# LED-Lamp-2-SMD-50leds.net
KiCad netlist of a schematic drawn in EAGLE
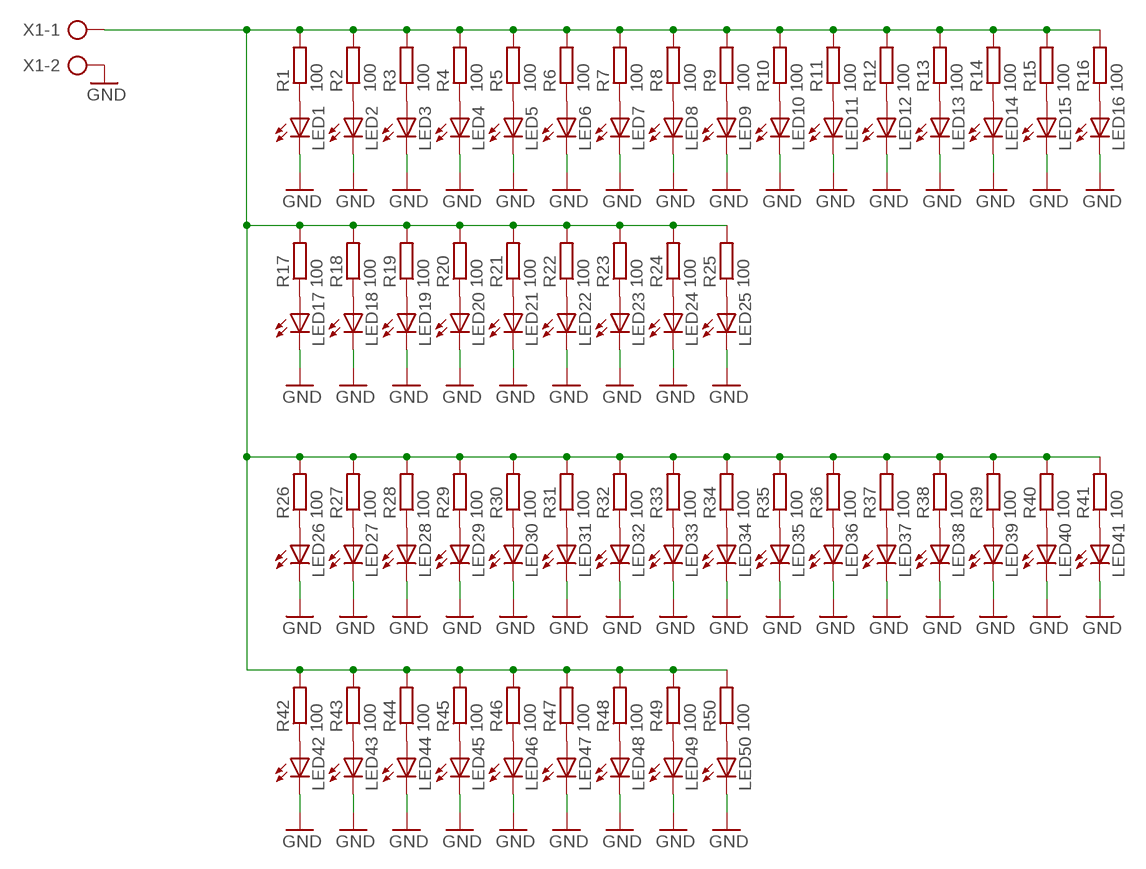
[diagram p0: schematic, sheet 1]

(export (version "E")
  (design (tool "Eeschema 10.0.6"))
  (components
    (comp (ref "LED1")
      (value "LEDSML0805")
      (footprint "eagle-import:SML0805")
      (libsource (lib "eagle-import") (part "LEDSML0805"))
    )
    (comp (ref "LED2")
      (value "LEDSML0805")
      (footprint "eagle-import:SML0805")
      (libsource (lib "eagle-import") (part "LEDSML0805"))
    )
    (comp (ref "LED3")
      (value "LEDSML0805")
      (footprint "eagle-import:SML0805")
      (libsource (lib "eagle-import") (part "LEDSML0805"))
    )
    (comp (ref "LED4")
      (value "LEDSML0805")
      (footprint "eagle-import:SML0805")
      (libsource (lib "eagle-import") (part "LEDSML0805"))
    )
    (comp (ref "LED5")
      (value "LEDSML0805")
      (footprint "eagle-import:SML0805")
      (libsource (lib "eagle-import") (part "LEDSML0805"))
    )
    (comp (ref "LED6")
      (value "LEDSML0805")
      (footprint "eagle-import:SML0805")
      (libsource (lib "eagle-import") (part "LEDSML0805"))
    )
    (comp (ref "LED7")
      (value "LEDSML0805")
      (footprint "eagle-import:SML0805")
      (libsource (lib "eagle-import") (part "LEDSML0805"))
    )
    (comp (ref "LED8")
      (value "LEDSML0805")
      (footprint "eagle-import:SML0805")
      (libsource (lib "eagle-import") (part "LEDSML0805"))
    )
    (comp (ref "LED9")
      (value "LEDSML0805")
      (footprint "eagle-import:SML0805")
      (libsource (lib "eagle-import") (part "LEDSML0805"))
    )
    (comp (ref "LED10")
      (value "LEDSML0805")
      (footprint "eagle-import:SML0805")
      (libsource (lib "eagle-import") (part "LEDSML0805"))
    )
    (comp (ref "LED11")
      (value "LEDSML0805")
      (footprint "eagle-import:SML0805")
      (libsource (lib "eagle-import") (part "LEDSML0805"))
    )
    (comp (ref "LED12")
      (value "LEDSML0805")
      (footprint "eagle-import:SML0805")
      (libsource (lib "eagle-import") (part "LEDSML0805"))
    )
    (comp (ref "LED13")
      (value "LEDSML0805")
      (footprint "eagle-import:SML0805")
      (libsource (lib "eagle-import") (part "LEDSML0805"))
    )
    (comp (ref "LED14")
      (value "LEDSML0805")
      (footprint "eagle-import:SML0805")
      (libsource (lib "eagle-import") (part "LEDSML0805"))
    )
    (comp (ref "LED15")
      (value "LEDSML0805")
      (footprint "eagle-import:SML0805")
      (libsource (lib "eagle-import") (part "LEDSML0805"))
    )
    (comp (ref "LED16")
      (value "LEDSML0805")
      (footprint "eagle-import:SML0805")
      (libsource (lib "eagle-import") (part "LEDSML0805"))
    )
    (comp (ref "LED17")
      (value "LEDSML0805")
      (footprint "eagle-import:SML0805")
      (libsource (lib "eagle-import") (part "LEDSML0805"))
    )
    (comp (ref "LED18")
      (value "LEDSML0805")
      (footprint "eagle-import:SML0805")
      (libsource (lib "eagle-import") (part "LEDSML0805"))
    )
    (comp (ref "LED19")
      (value "LEDSML0805")
      (footprint "eagle-import:SML0805")
      (libsource (lib "eagle-import") (part "LEDSML0805"))
    )
    (comp (ref "LED20")
      (value "LEDSML0805")
      (footprint "eagle-import:SML0805")
      (libsource (lib "eagle-import") (part "LEDSML0805"))
    )
    (comp (ref "LED21")
      (value "LEDSML0805")
      (footprint "eagle-import:SML0805")
      (libsource (lib "eagle-import") (part "LEDSML0805"))
    )
    (comp (ref "LED22")
      (value "LEDSML0805")
      (footprint "eagle-import:SML0805")
      (libsource (lib "eagle-import") (part "LEDSML0805"))
    )
    (comp (ref "LED23")
      (value "LEDSML0805")
      (footprint "eagle-import:SML0805")
      (libsource (lib "eagle-import") (part "LEDSML0805"))
    )
    (comp (ref "LED24")
      (value "LEDSML0805")
      (footprint "eagle-import:SML0805")
      (libsource (lib "eagle-import") (part "LEDSML0805"))
    )
    (comp (ref "LED25")
      (value "LEDSML0805")
      (footprint "eagle-import:SML0805")
      (libsource (lib "eagle-import") (part "LEDSML0805"))
    )
    (comp (ref "LED26")
      (value "LEDSML0805")
      (footprint "eagle-import:SML0805")
      (libsource (lib "eagle-import") (part "LEDSML0805"))
    )
    (comp (ref "LED27")
      (value "LEDSML0805")
      (footprint "eagle-import:SML0805")
      (libsource (lib "eagle-import") (part "LEDSML0805"))
    )
    (comp (ref "LED28")
      (value "LEDSML0805")
      (footprint "eagle-import:SML0805")
      (libsource (lib "eagle-import") (part "LEDSML0805"))
    )
    (comp (ref "LED29")
      (value "LEDSML0805")
      (footprint "eagle-import:SML0805")
      (libsource (lib "eagle-import") (part "LEDSML0805"))
    )
    (comp (ref "LED30")
      (value "LEDSML0805")
      (footprint "eagle-import:SML0805")
      (libsource (lib "eagle-import") (part "LEDSML0805"))
    )
    (comp (ref "LED31")
      (value "LEDSML0805")
      (footprint "eagle-import:SML0805")
      (libsource (lib "eagle-import") (part "LEDSML0805"))
    )
    (comp (ref "LED32")
      (value "LEDSML0805")
      (footprint "eagle-import:SML0805")
      (libsource (lib "eagle-import") (part "LEDSML0805"))
    )
    (comp (ref "LED33")
      (value "LEDSML0805")
      (footprint "eagle-import:SML0805")
      (libsource (lib "eagle-import") (part "LEDSML0805"))
    )
    (comp (ref "LED34")
      (value "LEDSML0805")
      (footprint "eagle-import:SML0805")
      (libsource (lib "eagle-import") (part "LEDSML0805"))
    )
    (comp (ref "LED35")
      (value "LEDSML0805")
      (footprint "eagle-import:SML0805")
      (libsource (lib "eagle-import") (part "LEDSML0805"))
    )
    (comp (ref "LED36")
      (value "LEDSML0805")
      (footprint "eagle-import:SML0805")
      (libsource (lib "eagle-import") (part "LEDSML0805"))
    )
    (comp (ref "LED37")
      (value "LEDSML0805")
      (footprint "eagle-import:SML0805")
      (libsource (lib "eagle-import") (part "LEDSML0805"))
    )
    (comp (ref "LED38")
      (value "LEDSML0805")
      (footprint "eagle-import:SML0805")
      (libsource (lib "eagle-import") (part "LEDSML0805"))
    )
    (comp (ref "LED39")
      (value "LEDSML0805")
      (footprint "eagle-import:SML0805")
      (libsource (lib "eagle-import") (part "LEDSML0805"))
    )
    (comp (ref "LED40")
      (value "LEDSML0805")
      (footprint "eagle-import:SML0805")
      (libsource (lib "eagle-import") (part "LEDSML0805"))
    )
    (comp (ref "LED41")
      (value "LEDSML0805")
      (footprint "eagle-import:SML0805")
      (libsource (lib "eagle-import") (part "LEDSML0805"))
    )
    (comp (ref "LED42")
      (value "LEDSML0805")
      (footprint "eagle-import:SML0805")
      (libsource (lib "eagle-import") (part "LEDSML0805"))
    )
    (comp (ref "LED43")
      (value "LEDSML0805")
      (footprint "eagle-import:SML0805")
      (libsource (lib "eagle-import") (part "LEDSML0805"))
    )
    (comp (ref "LED44")
      (value "LEDSML0805")
      (footprint "eagle-import:SML0805")
      (libsource (lib "eagle-import") (part "LEDSML0805"))
    )
    (comp (ref "LED45")
      (value "LEDSML0805")
      (footprint "eagle-import:SML0805")
      (libsource (lib "eagle-import") (part "LEDSML0805"))
    )
    (comp (ref "LED46")
      (value "LEDSML0805")
      (footprint "eagle-import:SML0805")
      (libsource (lib "eagle-import") (part "LEDSML0805"))
    )
    (comp (ref "LED47")
      (value "LEDSML0805")
      (footprint "eagle-import:SML0805")
      (libsource (lib "eagle-import") (part "LEDSML0805"))
    )
    (comp (ref "LED48")
      (value "LEDSML0805")
      (footprint "eagle-import:SML0805")
      (libsource (lib "eagle-import") (part "LEDSML0805"))
    )
    (comp (ref "LED49")
      (value "LEDSML0805")
      (footprint "eagle-import:SML0805")
      (libsource (lib "eagle-import") (part "LEDSML0805"))
    )
    (comp (ref "LED50")
      (value "LEDSML0805")
      (footprint "eagle-import:SML0805")
      (libsource (lib "eagle-import") (part "LEDSML0805"))
    )
    (comp (ref "R1")
      (value "100")
      (footprint "eagle-import:M0805")
      (libsource (lib "eagle-import") (part "R-EU_M0805"))
    )
    (comp (ref "R2")
      (value "100")
      (footprint "eagle-import:M0805")
      (libsource (lib "eagle-import") (part "R-EU_M0805"))
    )
    (comp (ref "R3")
      (value "100")
      (footprint "eagle-import:M0805")
      (libsource (lib "eagle-import") (part "R-EU_M0805"))
    )
    (comp (ref "R4")
      (value "100")
      (footprint "eagle-import:M0805")
      (libsource (lib "eagle-import") (part "R-EU_M0805"))
    )
    (comp (ref "R5")
      (value "100")
      (footprint "eagle-import:M0805")
      (libsource (lib "eagle-import") (part "R-EU_M0805"))
    )
    (comp (ref "R6")
      (value "100")
      (footprint "eagle-import:M0805")
      (libsource (lib "eagle-import") (part "R-EU_M0805"))
    )
    (comp (ref "R7")
      (value "100")
      (footprint "eagle-import:M0805")
      (libsource (lib "eagle-import") (part "R-EU_M0805"))
    )
    (comp (ref "R8")
      (value "100")
      (footprint "eagle-import:M0805")
      (libsource (lib "eagle-import") (part "R-EU_M0805"))
    )
    (comp (ref "R9")
      (value "100")
      (footprint "eagle-import:M0805")
      (libsource (lib "eagle-import") (part "R-EU_M0805"))
    )
    (comp (ref "R10")
      (value "100")
      (footprint "eagle-import:M0805")
      (libsource (lib "eagle-import") (part "R-EU_M0805"))
    )
    (comp (ref "R11")
      (value "100")
      (footprint "eagle-import:M0805")
      (libsource (lib "eagle-import") (part "R-EU_M0805"))
    )
    (comp (ref "R12")
      (value "100")
      (footprint "eagle-import:M0805")
      (libsource (lib "eagle-import") (part "R-EU_M0805"))
    )
    (comp (ref "R13")
      (value "100")
      (footprint "eagle-import:M0805")
      (libsource (lib "eagle-import") (part "R-EU_M0805"))
    )
    (comp (ref "R14")
      (value "100")
      (footprint "eagle-import:M0805")
      (libsource (lib "eagle-import") (part "R-EU_M0805"))
    )
    (comp (ref "R15")
      (value "100")
      (footprint "eagle-import:M0805")
      (libsource (lib "eagle-import") (part "R-EU_M0805"))
    )
    (comp (ref "R16")
      (value "100")
      (footprint "eagle-import:M0805")
      (libsource (lib "eagle-import") (part "R-EU_M0805"))
    )
    (comp (ref "R17")
      (value "100")
      (footprint "eagle-import:M0805")
      (libsource (lib "eagle-import") (part "R-EU_M0805"))
    )
    (comp (ref "R18")
      (value "100")
      (footprint "eagle-import:M0805")
      (libsource (lib "eagle-import") (part "R-EU_M0805"))
    )
    (comp (ref "R19")
      (value "100")
      (footprint "eagle-import:M0805")
      (libsource (lib "eagle-import") (part "R-EU_M0805"))
    )
    (comp (ref "R20")
      (value "100")
      (footprint "eagle-import:M0805")
      (libsource (lib "eagle-import") (part "R-EU_M0805"))
    )
    (comp (ref "R21")
      (value "100")
      (footprint "eagle-import:M0805")
      (libsource (lib "eagle-import") (part "R-EU_M0805"))
    )
    (comp (ref "R22")
      (value "100")
      (footprint "eagle-import:M0805")
      (libsource (lib "eagle-import") (part "R-EU_M0805"))
    )
    (comp (ref "R23")
      (value "100")
      (footprint "eagle-import:M0805")
      (libsource (lib "eagle-import") (part "R-EU_M0805"))
    )
    (comp (ref "R24")
      (value "100")
      (footprint "eagle-import:M0805")
      (libsource (lib "eagle-import") (part "R-EU_M0805"))
    )
    (comp (ref "R25")
      (value "100")
      (footprint "eagle-import:M0805")
      (libsource (lib "eagle-import") (part "R-EU_M0805"))
    )
    (comp (ref "R26")
      (value "100")
      (footprint "eagle-import:M0805")
      (libsource (lib "eagle-import") (part "R-EU_M0805"))
    )
    (comp (ref "R27")
      (value "100")
      (footprint "eagle-import:M0805")
      (libsource (lib "eagle-import") (part "R-EU_M0805"))
    )
    (comp (ref "R28")
      (value "100")
      (footprint "eagle-import:M0805")
      (libsource (lib "eagle-import") (part "R-EU_M0805"))
    )
    (comp (ref "R29")
      (value "100")
      (footprint "eagle-import:M0805")
      (libsource (lib "eagle-import") (part "R-EU_M0805"))
    )
    (comp (ref "R30")
      (value "100")
      (footprint "eagle-import:M0805")
      (libsource (lib "eagle-import") (part "R-EU_M0805"))
    )
    (comp (ref "R31")
      (value "100")
      (footprint "eagle-import:M0805")
      (libsource (lib "eagle-import") (part "R-EU_M0805"))
    )
    (comp (ref "R32")
      (value "100")
      (footprint "eagle-import:M0805")
      (libsource (lib "eagle-import") (part "R-EU_M0805"))
    )
    (comp (ref "R33")
      (value "100")
      (footprint "eagle-import:M0805")
      (libsource (lib "eagle-import") (part "R-EU_M0805"))
    )
    (comp (ref "R34")
      (value "100")
      (footprint "eagle-import:M0805")
      (libsource (lib "eagle-import") (part "R-EU_M0805"))
    )
    (comp (ref "R35")
      (value "100")
      (footprint "eagle-import:M0805")
      (libsource (lib "eagle-import") (part "R-EU_M0805"))
    )
    (comp (ref "R36")
      (value "100")
      (footprint "eagle-import:M0805")
      (libsource (lib "eagle-import") (part "R-EU_M0805"))
    )
    (comp (ref "R37")
      (value "100")
      (footprint "eagle-import:M0805")
      (libsource (lib "eagle-import") (part "R-EU_M0805"))
    )
    (comp (ref "R38")
      (value "100")
      (footprint "eagle-import:M0805")
      (libsource (lib "eagle-import") (part "R-EU_M0805"))
    )
    (comp (ref "R39")
      (value "100")
      (footprint "eagle-import:M0805")
      (libsource (lib "eagle-import") (part "R-EU_M0805"))
    )
    (comp (ref "R40")
      (value "100")
      (footprint "eagle-import:M0805")
      (libsource (lib "eagle-import") (part "R-EU_M0805"))
    )
    (comp (ref "R41")
      (value "100")
      (footprint "eagle-import:M0805")
      (libsource (lib "eagle-import") (part "R-EU_M0805"))
    )
    (comp (ref "R42")
      (value "100")
      (footprint "eagle-import:M0805")
      (libsource (lib "eagle-import") (part "R-EU_M0805"))
    )
    (comp (ref "R43")
      (value "100")
      (footprint "eagle-import:M0805")
      (libsource (lib "eagle-import") (part "R-EU_M0805"))
    )
    (comp (ref "R44")
      (value "100")
      (footprint "eagle-import:M0805")
      (libsource (lib "eagle-import") (part "R-EU_M0805"))
    )
    (comp (ref "R45")
      (value "100")
      (footprint "eagle-import:M0805")
      (libsource (lib "eagle-import") (part "R-EU_M0805"))
    )
    (comp (ref "R46")
      (value "100")
      (footprint "eagle-import:M0805")
      (libsource (lib "eagle-import") (part "R-EU_M0805"))
    )
    (comp (ref "R47")
      (value "100")
      (footprint "eagle-import:M0805")
      (libsource (lib "eagle-import") (part "R-EU_M0805"))
    )
    (comp (ref "R48")
      (value "100")
      (footprint "eagle-import:M0805")
      (libsource (lib "eagle-import") (part "R-EU_M0805"))
    )
    (comp (ref "R49")
      (value "100")
      (footprint "eagle-import:M0805")
      (libsource (lib "eagle-import") (part "R-EU_M0805"))
    )
    (comp (ref "R50")
      (value "100")
      (footprint "eagle-import:M0805")
      (libsource (lib "eagle-import") (part "R-EU_M0805"))
    )
    (comp (ref "X1")
      (value "AK300/2")
      (footprint "eagle-import:AK300_2")
      (libsource (lib "eagle-import") (part "AK300/2"))
    )
  )
  (nets
    (net (code "1") (name "GND") (class "Default")
      (node (ref "LED1") (pin "C") (pinfunction "C_C") (pintype "passive"))
      (node (ref "LED10") (pin "C") (pinfunction "C_C") (pintype "passive"))
      (node (ref "LED11") (pin "C") (pinfunction "C_C") (pintype "passive"))
      (node (ref "LED12") (pin "C") (pinfunction "C_C") (pintype "passive"))
      (node (ref "LED13") (pin "C") (pinfunction "C_C") (pintype "passive"))
      (node (ref "LED14") (pin "C") (pinfunction "C_C") (pintype "passive"))
      (node (ref "LED15") (pin "C") (pinfunction "C_C") (pintype "passive"))
      (node (ref "LED16") (pin "C") (pinfunction "C_C") (pintype "passive"))
      (node (ref "LED17") (pin "C") (pinfunction "C_C") (pintype "passive"))
      (node (ref "LED18") (pin "C") (pinfunction "C_C") (pintype "passive"))
      (node (ref "LED19") (pin "C") (pinfunction "C_C") (pintype "passive"))
      (node (ref "LED2") (pin "C") (pinfunction "C_C") (pintype "passive"))
      (node (ref "LED20") (pin "C") (pinfunction "C_C") (pintype "passive"))
      (node (ref "LED21") (pin "C") (pinfunction "C_C") (pintype "passive"))
      (node (ref "LED22") (pin "C") (pinfunction "C_C") (pintype "passive"))
      (node (ref "LED23") (pin "C") (pinfunction "C_C") (pintype "passive"))
      (node (ref "LED24") (pin "C") (pinfunction "C_C") (pintype "passive"))
      (node (ref "LED25") (pin "C") (pinfunction "C_C") (pintype "passive"))
      (node (ref "LED26") (pin "C") (pinfunction "C_C") (pintype "passive"))
      (node (ref "LED27") (pin "C") (pinfunction "C_C") (pintype "passive"))
      (node (ref "LED28") (pin "C") (pinfunction "C_C") (pintype "passive"))
      (node (ref "LED29") (pin "C") (pinfunction "C_C") (pintype "passive"))
      (node (ref "LED3") (pin "C") (pinfunction "C_C") (pintype "passive"))
      (node (ref "LED30") (pin "C") (pinfunction "C_C") (pintype "passive"))
      (node (ref "LED31") (pin "C") (pinfunction "C_C") (pintype "passive"))
      (node (ref "LED32") (pin "C") (pinfunction "C_C") (pintype "passive"))
      (node (ref "LED33") (pin "C") (pinfunction "C_C") (pintype "passive"))
      (node (ref "LED34") (pin "C") (pinfunction "C_C") (pintype "passive"))
      (node (ref "LED35") (pin "C") (pinfunction "C_C") (pintype "passive"))
      (node (ref "LED36") (pin "C") (pinfunction "C_C") (pintype "passive"))
      (node (ref "LED37") (pin "C") (pinfunction "C_C") (pintype "passive"))
      (node (ref "LED38") (pin "C") (pinfunction "C_C") (pintype "passive"))
      (node (ref "LED39") (pin "C") (pinfunction "C_C") (pintype "passive"))
      (node (ref "LED4") (pin "C") (pinfunction "C_C") (pintype "passive"))
      (node (ref "LED40") (pin "C") (pinfunction "C_C") (pintype "passive"))
      (node (ref "LED41") (pin "C") (pinfunction "C_C") (pintype "passive"))
      (node (ref "LED42") (pin "C") (pinfunction "C_C") (pintype "passive"))
      (node (ref "LED43") (pin "C") (pinfunction "C_C") (pintype "passive"))
      (node (ref "LED44") (pin "C") (pinfunction "C_C") (pintype "passive"))
      (node (ref "LED45") (pin "C") (pinfunction "C_C") (pintype "passive"))
      (node (ref "LED46") (pin "C") (pinfunction "C_C") (pintype "passive"))
      (node (ref "LED47") (pin "C") (pinfunction "C_C") (pintype "passive"))
      (node (ref "LED48") (pin "C") (pinfunction "C_C") (pintype "passive"))
      (node (ref "LED49") (pin "C") (pinfunction "C_C") (pintype "passive"))
      (node (ref "LED5") (pin "C") (pinfunction "C_C") (pintype "passive"))
      (node (ref "LED50") (pin "C") (pinfunction "C_C") (pintype "passive"))
      (node (ref "LED6") (pin "C") (pinfunction "C_C") (pintype "passive"))
      (node (ref "LED7") (pin "C") (pinfunction "C_C") (pintype "passive"))
      (node (ref "LED8") (pin "C") (pinfunction "C_C") (pintype "passive"))
      (node (ref "LED9") (pin "C") (pinfunction "C_C") (pintype "passive"))
      (node (ref "X1") (pin "2") (pinfunction "KL_2") (pintype "passive"))
    )
    (net (code "2") (name "Net-(LED1-PadA)") (class "Default")
      (node (ref "LED1") (pin "A") (pinfunction "A_A") (pintype "passive"))
      (node (ref "R1") (pin "1") (pinfunction "1_1") (pintype "passive"))
    )
    (net (code "3") (name "Net-(LED2-PadA)") (class "Default")
      (node (ref "LED2") (pin "A") (pinfunction "A_A") (pintype "passive"))
      (node (ref "R2") (pin "1") (pinfunction "1_1") (pintype "passive"))
    )
    (net (code "4") (name "Net-(LED3-PadA)") (class "Default")
      (node (ref "LED3") (pin "A") (pinfunction "A_A") (pintype "passive"))
      (node (ref "R3") (pin "1") (pinfunction "1_1") (pintype "passive"))
    )
    (net (code "5") (name "Net-(LED4-PadA)") (class "Default")
      (node (ref "LED4") (pin "A") (pinfunction "A_A") (pintype "passive"))
      (node (ref "R4") (pin "1") (pinfunction "1_1") (pintype "passive"))
    )
    (net (code "6") (name "Net-(LED5-PadA)") (class "Default")
      (node (ref "LED5") (pin "A") (pinfunction "A_A") (pintype "passive"))
      (node (ref "R5") (pin "1") (pinfunction "1_1") (pintype "passive"))
    )
    (net (code "7") (name "Net-(LED6-PadA)") (class "Default")
      (node (ref "LED6") (pin "A") (pinfunction "A_A") (pintype "passive"))
      (node (ref "R6") (pin "1") (pinfunction "1_1") (pintype "passive"))
    )
    (net (code "8") (name "Net-(LED7-PadA)") (class "Default")
      (node (ref "LED7") (pin "A") (pinfunction "A_A") (pintype "passive"))
      (node (ref "R7") (pin "1") (pinfunction "1_1") (pintype "passive"))
    )
    (net (code "9") (name "Net-(LED8-PadA)") (class "Default")
      (node (ref "LED8") (pin "A") (pinfunction "A_A") (pintype "passive"))
      (node (ref "R8") (pin "1") (pinfunction "1_1") (pintype "passive"))
    )
    (net (code "10") (name "Net-(LED9-PadA)") (class "Default")
      (node (ref "LED9") (pin "A") (pinfunction "A_A") (pintype "passive"))
      (node (ref "R9") (pin "1") (pinfunction "1_1") (pintype "passive"))
    )
    (net (code "11") (name "Net-(LED10-PadA)") (class "Default")
      (node (ref "LED10") (pin "A") (pinfunction "A_A") (pintype "passive"))
      (node (ref "R10") (pin "1") (pinfunction "1_1") (pintype "passive"))
    )
    (net (code "12") (name "Net-(LED11-PadA)") (class "Default")
      (node (ref "LED11") (pin "A") (pinfunction "A_A") (pintype "passive"))
      (node (ref "R11") (pin "1") (pinfunction "1_1") (pintype "passive"))
    )
    (net (code "13") (name "Net-(LED12-PadA)") (class "Default")
      (node (ref "LED12") (pin "A") (pinfunction "A_A") (pintype "passive"))
      (node (ref "R12") (pin "1") (pinfunction "1_1") (pintype "passive"))
    )
    (net (code "14") (name "Net-(LED13-PadA)") (class "Default")
      (node (ref "LED13") (pin "A") (pinfunction "A_A") (pintype "passive"))
      (node (ref "R13") (pin "1") (pinfunction "1_1") (pintype "passive"))
    )
    (net (code "15") (name "Net-(LED14-PadA)") (class "Default")
      (node (ref "LED14") (pin "A") (pinfunction "A_A") (pintype "passive"))
      (node (ref "R14") (pin "1") (pinfunction "1_1") (pintype "passive"))
    )
    (net (code "16") (name "Net-(LED15-PadA)") (class "Default")
      (node (ref "LED15") (pin "A") (pinfunction "A_A") (pintype "passive"))
      (node (ref "R15") (pin "1") (pinfunction "1_1") (pintype "passive"))
    )
    (net (code "17") (name "Net-(LED16-PadA)") (class "Default")
      (node (ref "LED16") (pin "A") (pinfunction "A_A") (pintype "passive"))
      (node (ref "R16") (pin "1") (pinfunction "1_1") (pintype "passive"))
    )
    (net (code "18") (name "Net-(LED17-PadA)") (class "Default")
      (node (ref "LED17") (pin "A") (pinfunction "A_A") (pintype "passive"))
      (node (ref "R17") (pin "1") (pinfunction "1_1") (pintype "passive"))
    )
    (net (code "19") (name "Net-(LED18-PadA)") (class "Default")
      (node (ref "LED18") (pin "A") (pinfunction "A_A") (pintype "passive"))
      (node (ref "R18") (pin "1") (pinfunction "1_1") (pintype "passive"))
    )
    (net (code "20") (name "Net-(LED19-PadA)") (class "Default")
      (node (ref "LED19") (pin "A") (pinfunction "A_A") (pintype "passive"))
      (node (ref "R19") (pin "1") (pinfunction "1_1") (pintype "passive"))
    )
    (net (code "21") (name "Net-(LED20-PadA)") (class "Default")
      (node (ref "LED20") (pin "A") (pinfunction "A_A") (pintype "passive"))
      (node (ref "R20") (pin "1") (pinfunction "1_1") (pintype "passive"))
    )
    (net (code "22") (name "Net-(LED21-PadA)") (class "Default")
      (node (ref "LED21") (pin "A") (pinfunction "A_A") (pintype "passive"))
      (node (ref "R21") (pin "1") (pinfunction "1_1") (pintype "passive"))
    )
    (net (code "23") (name "Net-(LED22-PadA)") (class "Default")
      (node (ref "LED22") (pin "A") (pinfunction "A_A") (pintype "passive"))
      (node (ref "R22") (pin "1") (pinfunction "1_1") (pintype "passive"))
    )
    (net (code "24") (name "Net-(LED23-PadA)") (class "Default")
      (node (ref "LED23") (pin "A") (pinfunction "A_A") (pintype "passive"))
      (node (ref "R23") (pin "1") (pinfunction "1_1") (pintype "passive"))
    )
    (net (code "25") (name "Net-(LED24-PadA)") (class "Default")
      (node (ref "LED24") (pin "A") (pinfunction "A_A") (pintype "passive"))
      (node (ref "R24") (pin "1") (pinfunction "1_1") (pintype "passive"))
    )
    (net (code "26") (name "Net-(LED25-PadA)") (class "Default")
      (node (ref "LED25") (pin "A") (pinfunction "A_A") (pintype "passive"))
      (node (ref "R25") (pin "1") (pinfunction "1_1") (pintype "passive"))
    )
    (net (code "27") (name "Net-(LED26-PadA)") (class "Default")
      (node (ref "LED26") (pin "A") (pinfunction "A_A") (pintype "passive"))
      (node (ref "R26") (pin "1") (pinfunction "1_1") (pintype "passive"))
    )
    (net (code "28") (name "Net-(LED27-PadA)") (class "Default")
      (node (ref "LED27") (pin "A") (pinfunction "A_A") (pintype "passive"))
      (node (ref "R27") (pin "1") (pinfunction "1_1") (pintype "passive"))
    )
    (net (code "29") (name "Net-(LED28-PadA)") (class "Default")
      (node (ref "LED28") (pin "A") (pinfunction "A_A") (pintype "passive"))
      (node (ref "R28") (pin "1") (pinfunction "1_1") (pintype "passive"))
    )
    (net (code "30") (name "Net-(LED29-PadA)") (class "Default")
      (node (ref "LED29") (pin "A") (pinfunction "A_A") (pintype "passive"))
      (node (ref "R29") (pin "1") (pinfunction "1_1") (pintype "passive"))
    )
    (net (code "31") (name "Net-(LED30-PadA)") (class "Default")
      (node (ref "LED30") (pin "A") (pinfunction "A_A") (pintype "passive"))
      (node (ref "R30") (pin "1") (pinfunction "1_1") (pintype "passive"))
    )
    (net (code "32") (name "Net-(LED31-PadA)") (class "Default")
      (node (ref "LED31") (pin "A") (pinfunction "A_A") (pintype "passive"))
      (node (ref "R31") (pin "1") (pinfunction "1_1") (pintype "passive"))
    )
    (net (code "33") (name "Net-(LED32-PadA)") (class "Default")
      (node (ref "LED32") (pin "A") (pinfunction "A_A") (pintype "passive"))
      (node (ref "R32") (pin "1") (pinfunction "1_1") (pintype "passive"))
    )
    (net (code "34") (name "Net-(LED33-PadA)") (class "Default")
      (node (ref "LED33") (pin "A") (pinfunction "A_A") (pintype "passive"))
      (node (ref "R33") (pin "1") (pinfunction "1_1") (pintype "passive"))
    )
    (net (code "35") (name "Net-(LED34-PadA)") (class "Default")
      (node (ref "LED34") (pin "A") (pinfunction "A_A") (pintype "passive"))
      (node (ref "R34") (pin "1") (pinfunction "1_1") (pintype "passive"))
    )
    (net (code "36") (name "Net-(LED35-PadA)") (class "Default")
      (node (ref "LED35") (pin "A") (pinfunction "A_A") (pintype "passive"))
      (node (ref "R35") (pin "1") (pinfunction "1_1") (pintype "passive"))
    )
    (net (code "37") (name "Net-(LED36-PadA)") (class "Default")
      (node (ref "LED36") (pin "A") (pinfunction "A_A") (pintype "passive"))
      (node (ref "R36") (pin "1") (pinfunction "1_1") (pintype "passive"))
    )
    (net (code "38") (name "Net-(LED37-PadA)") (class "Default")
      (node (ref "LED37") (pin "A") (pinfunction "A_A") (pintype "passive"))
      (node (ref "R37") (pin "1") (pinfunction "1_1") (pintype "passive"))
    )
    (net (code "39") (name "Net-(LED38-PadA)") (class "Default")
      (node (ref "LED38") (pin "A") (pinfunction "A_A") (pintype "passive"))
      (node (ref "R38") (pin "1") (pinfunction "1_1") (pintype "passive"))
    )
    (net (code "40") (name "Net-(LED39-PadA)") (class "Default")
      (node (ref "LED39") (pin "A") (pinfunction "A_A") (pintype "passive"))
      (node (ref "R39") (pin "1") (pinfunction "1_1") (pintype "passive"))
    )
    (net (code "41") (name "Net-(LED40-PadA)") (class "Default")
      (node (ref "LED40") (pin "A") (pinfunction "A_A") (pintype "passive"))
      (node (ref "R40") (pin "1") (pinfunction "1_1") (pintype "passive"))
    )
    (net (code "42") (name "Net-(LED41-PadA)") (class "Default")
      (node (ref "LED41") (pin "A") (pinfunction "A_A") (pintype "passive"))
      (node (ref "R41") (pin "1") (pinfunction "1_1") (pintype "passive"))
    )
    (net (code "43") (name "Net-(LED42-PadA)") (class "Default")
      (node (ref "LED42") (pin "A") (pinfunction "A_A") (pintype "passive"))
      (node (ref "R42") (pin "1") (pinfunction "1_1") (pintype "passive"))
    )
    (net (code "44") (name "Net-(LED43-PadA)") (class "Default")
      (node (ref "LED43") (pin "A") (pinfunction "A_A") (pintype "passive"))
      (node (ref "R43") (pin "1") (pinfunction "1_1") (pintype "passive"))
    )
    (net (code "45") (name "Net-(LED44-PadA)") (class "Default")
      (node (ref "LED44") (pin "A") (pinfunction "A_A") (pintype "passive"))
      (node (ref "R44") (pin "1") (pinfunction "1_1") (pintype "passive"))
    )
    (net (code "46") (name "Net-(LED45-PadA)") (class "Default")
      (node (ref "LED45") (pin "A") (pinfunction "A_A") (pintype "passive"))
      (node (ref "R45") (pin "1") (pinfunction "1_1") (pintype "passive"))
    )
    (net (code "47") (name "Net-(LED46-PadA)") (class "Default")
      (node (ref "LED46") (pin "A") (pinfunction "A_A") (pintype "passive"))
      (node (ref "R46") (pin "1") (pinfunction "1_1") (pintype "passive"))
    )
    (net (code "48") (name "Net-(LED47-PadA)") (class "Default")
      (node (ref "LED47") (pin "A") (pinfunction "A_A") (pintype "passive"))
      (node (ref "R47") (pin "1") (pinfunction "1_1") (pintype "passive"))
    )
    (net (code "49") (name "Net-(LED48-PadA)") (class "Default")
      (node (ref "LED48") (pin "A") (pinfunction "A_A") (pintype "passive"))
      (node (ref "R48") (pin "1") (pinfunction "1_1") (pintype "passive"))
    )
    (net (code "50") (name "Net-(LED49-PadA)") (class "Default")
      (node (ref "LED49") (pin "A") (pinfunction "A_A") (pintype "passive"))
      (node (ref "R49") (pin "1") (pinfunction "1_1") (pintype "passive"))
    )
    (net (code "51") (name "Net-(LED50-PadA)") (class "Default")
      (node (ref "LED50") (pin "A") (pinfunction "A_A") (pintype "passive"))
      (node (ref "R50") (pin "1") (pinfunction "1_1") (pintype "passive"))
    )
    (net (code "52") (name "Net-(X1A-KL)") (class "Default")
      (node (ref "R1") (pin "2") (pinfunction "2_2") (pintype "passive"))
      (node (ref "R10") (pin "2") (pinfunction "2_2") (pintype "passive"))
      (node (ref "R11") (pin "2") (pinfunction "2_2") (pintype "passive"))
      (node (ref "R12") (pin "2") (pinfunction "2_2") (pintype "passive"))
      (node (ref "R13") (pin "2") (pinfunction "2_2") (pintype "passive"))
      (node (ref "R14") (pin "2") (pinfunction "2_2") (pintype "passive"))
      (node (ref "R15") (pin "2") (pinfunction "2_2") (pintype "passive"))
      (node (ref "R16") (pin "2") (pinfunction "2_2") (pintype "passive"))
      (node (ref "R17") (pin "2") (pinfunction "2_2") (pintype "passive"))
      (node (ref "R18") (pin "2") (pinfunction "2_2") (pintype "passive"))
      (node (ref "R19") (pin "2") (pinfunction "2_2") (pintype "passive"))
      (node (ref "R2") (pin "2") (pinfunction "2_2") (pintype "passive"))
      (node (ref "R20") (pin "2") (pinfunction "2_2") (pintype "passive"))
      (node (ref "R21") (pin "2") (pinfunction "2_2") (pintype "passive"))
      (node (ref "R22") (pin "2") (pinfunction "2_2") (pintype "passive"))
      (node (ref "R23") (pin "2") (pinfunction "2_2") (pintype "passive"))
      (node (ref "R24") (pin "2") (pinfunction "2_2") (pintype "passive"))
      (node (ref "R25") (pin "2") (pinfunction "2_2") (pintype "passive"))
      (node (ref "R26") (pin "2") (pinfunction "2_2") (pintype "passive"))
      (node (ref "R27") (pin "2") (pinfunction "2_2") (pintype "passive"))
      (node (ref "R28") (pin "2") (pinfunction "2_2") (pintype "passive"))
      (node (ref "R29") (pin "2") (pinfunction "2_2") (pintype "passive"))
      (node (ref "R3") (pin "2") (pinfunction "2_2") (pintype "passive"))
      (node (ref "R30") (pin "2") (pinfunction "2_2") (pintype "passive"))
      (node (ref "R31") (pin "2") (pinfunction "2_2") (pintype "passive"))
      (node (ref "R32") (pin "2") (pinfunction "2_2") (pintype "passive"))
      (node (ref "R33") (pin "2") (pinfunction "2_2") (pintype "passive"))
      (node (ref "R34") (pin "2") (pinfunction "2_2") (pintype "passive"))
      (node (ref "R35") (pin "2") (pinfunction "2_2") (pintype "passive"))
      (node (ref "R36") (pin "2") (pinfunction "2_2") (pintype "passive"))
      (node (ref "R37") (pin "2") (pinfunction "2_2") (pintype "passive"))
      (node (ref "R38") (pin "2") (pinfunction "2_2") (pintype "passive"))
      (node (ref "R39") (pin "2") (pinfunction "2_2") (pintype "passive"))
      (node (ref "R4") (pin "2") (pinfunction "2_2") (pintype "passive"))
      (node (ref "R40") (pin "2") (pinfunction "2_2") (pintype "passive"))
      (node (ref "R41") (pin "2") (pinfunction "2_2") (pintype "passive"))
      (node (ref "R42") (pin "2") (pinfunction "2_2") (pintype "passive"))
      (node (ref "R43") (pin "2") (pinfunction "2_2") (pintype "passive"))
      (node (ref "R44") (pin "2") (pinfunction "2_2") (pintype "passive"))
      (node (ref "R45") (pin "2") (pinfunction "2_2") (pintype "passive"))
      (node (ref "R46") (pin "2") (pinfunction "2_2") (pintype "passive"))
      (node (ref "R47") (pin "2") (pinfunction "2_2") (pintype "passive"))
      (node (ref "R48") (pin "2") (pinfunction "2_2") (pintype "passive"))
      (node (ref "R49") (pin "2") (pinfunction "2_2") (pintype "passive"))
      (node (ref "R5") (pin "2") (pinfunction "2_2") (pintype "passive"))
      (node (ref "R50") (pin "2") (pinfunction "2_2") (pintype "passive"))
      (node (ref "R6") (pin "2") (pinfunction "2_2") (pintype "passive"))
      (node (ref "R7") (pin "2") (pinfunction "2_2") (pintype "passive"))
      (node (ref "R8") (pin "2") (pinfunction "2_2") (pintype "passive"))
      (node (ref "R9") (pin "2") (pinfunction "2_2") (pintype "passive"))
      (node (ref "X1") (pin "1") (pinfunction "KL_1") (pintype "passive"))
    )
  )
)
